# Debug.net
KiCad netlist of a schematic drawn in Altium Designer
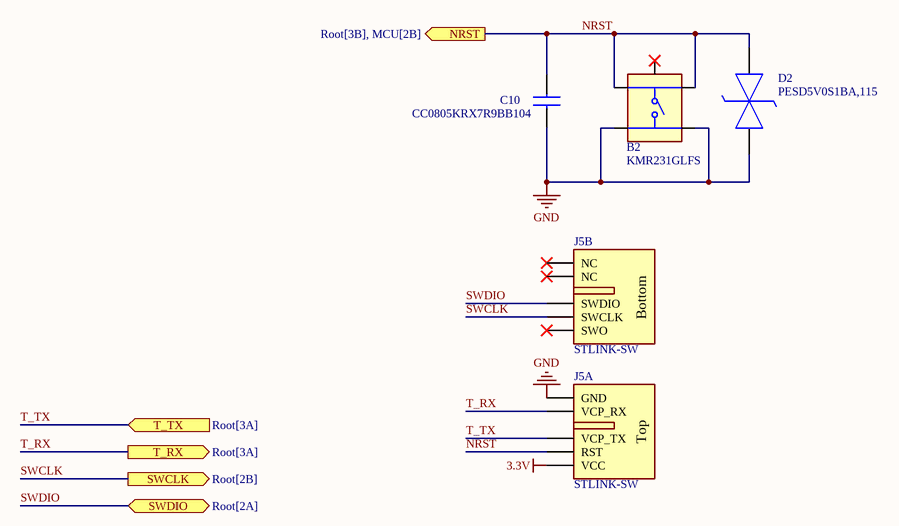
[diagram p0: Debug.SchDoc]

(export (version "E")
  (design (tool "Eeschema 10.0.6"))
  (components
    (comp (ref "B2")
      (value "KMR231GLFS")
      (footprint "KMR231GLFS")
      (description "Tactile Switch SPST 300gf 1.9mm Gull Wing 4.6mm x 2.8mm Surface Mount")
      (fields (field (name "LCSC PART #") "C99271"))
      (libsource (lib "MaUWB") (part "KMR231GLFS"))
    )
    (comp (ref "C10")
      (value "CC0805KRX7R9BB104")
      (footprint "CAPC2012X95N")
      (description "100nF, 0805, X7R")
      (fields (field (name "LCSC PART #") "C49678"))
      (libsource (lib "MaUWB") (part "CC0805KRX7R9BB104"))
    )
    (comp (ref "D2")
      (value "PESD5V0S1BA,115")
      (footprint "SOD2512X110N")
      (description "14VC Clamp 12A@8/20us Ipp ESD DIODE SOD-323")
      (fields (field (name "LCSC PART #") "C19224"))
      (libsource (lib "MaUWB") (part "PESD5V0S1BA,115"))
    )
    (comp (ref "J5")
      (value "STLINK-SW")
      (footprint "009159010061911")
      (description "SSL Connector 10 Position Adapter, Bridge Board to Board - Card Edge 0.079\" (2.00mm)")
      (libsource (lib "MaUWB") (part "STLINK-SW"))
    )
  )
  (nets
    (net (code "1") (name "/NRST") (class "Default")
      (node (ref "B2") (pin "1") (pinfunction "1_1") (pintype "passive"))
      (node (ref "B2") (pin "2") (pinfunction "2_2") (pintype "passive"))
      (node (ref "C10") (pin "2") (pinfunction "2_2") (pintype "passive"))
      (node (ref "D2") (pin "2") (pinfunction "K2_2") (pintype "passive"))
      (node (ref "J5") (pin "4") (pinfunction "RST_4") (pintype "passive"))
    )
    (net (code "2") (name "/SWCLK") (class "Default")
      (node (ref "J5") (pin "9") (pinfunction "SWCLK_9") (pintype "passive"))
    )
    (net (code "3") (name "/SWDIO") (class "Default")
      (node (ref "J5") (pin "8") (pinfunction "SWDIO_8") (pintype "passive"))
    )
    (net (code "4") (name "/T_RX") (class "Default")
      (node (ref "J5") (pin "2") (pinfunction "VCP_RX_2") (pintype "passive"))
    )
    (net (code "5") (name "/T_TX") (class "Default")
      (node (ref "J5") (pin "3") (pinfunction "VCP_TX_3") (pintype "passive"))
    )
    (net (code "6") (name "3.3V") (class "Default")
      (node (ref "J5") (pin "5") (pinfunction "VCC_5") (pintype "passive"))
    )
    (net (code "7") (name "GND") (class "Default")
      (node (ref "B2") (pin "3") (pinfunction "3_3") (pintype "passive"))
      (node (ref "B2") (pin "4") (pinfunction "4_4") (pintype "passive"))
      (node (ref "C10") (pin "1") (pinfunction "1_1") (pintype "passive"))
      (node (ref "D2") (pin "1") (pinfunction "K1_1") (pintype "passive"))
      (node (ref "J5") (pin "1") (pinfunction "GND_1") (pintype "passive"))
    )
    (net (code "8") (name "unconnected-(B2-Pad5)") (class "Default")
      (node (ref "B2") (pin "5") (pinfunction "5_5") (pintype "passive+no_connect"))
    )
    (net (code "9") (name "unconnected-(J5B-NC-Pad6)") (class "Default")
      (node (ref "J5") (pin "6") (pinfunction "NC_6") (pintype "passive+no_connect"))
    )
    (net (code "10") (name "unconnected-(J5B-NC-Pad7)") (class "Default")
      (node (ref "J5") (pin "7") (pinfunction "NC_7") (pintype "passive+no_connect"))
    )
    (net (code "11") (name "unconnected-(J5B-SWO-Pad10)") (class "Default")
      (node (ref "J5") (pin "10") (pinfunction "SWO_10") (pintype "passive+no_connect"))
    )
  )
)
